# IR_sensor_new_v2.net
KiCad netlist of a schematic drawn in EAGLE
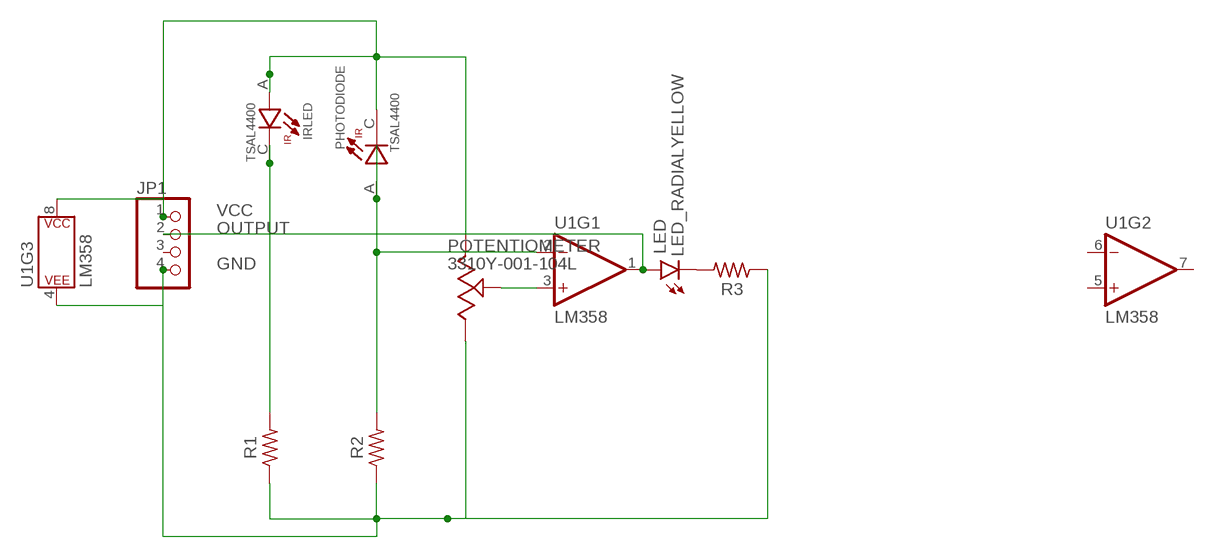
[diagram p0: schematic, sheet 1]

(export (version "E")
  (design (tool "Eeschema 10.0.6"))
  (components
    (comp (ref "IRLED")
      (value "TSAL4400")
      (footprint "eagle-import:LEDRD254W45D335H610")
      (fields (field (name "MF") "Vishay Semiconductor"))
      (libsource (lib "eagle-import") (part "TSAL4400"))
    )
    (comp (ref "JP1")
      (value "PINHD-1X4/90")
      (footprint "eagle-import:1X04_90")
      (libsource (lib "eagle-import") (part "PINHD-1X4/90"))
    )
    (comp (ref "LED")
      (value "LED_RADIALYELLOW")
      (footprint "eagle-import:LEDRD254W60D565H860B_Y")
      (libsource (lib "eagle-import") (part "LED_RADIALYELLOW"))
    )
    (comp (ref "PHOTODIODE")
      (value "TSAL4400")
      (footprint "eagle-import:LEDRD254W45D335H610")
      (fields (field (name "MF") "Vishay Semiconductor"))
      (libsource (lib "eagle-import") (part "TSAL4400"))
    )
    (comp (ref "POTENTIOMETER")
      (value "3310Y-001-104L")
      (footprint "eagle-import:3310Y-001-104L-ND")
      (fields
        (field (name "DIGIKEY_PARTNO") "3310Y-001-104L-ND")
        (field (name "MANUFACTURER") "Bourns Inc.")
        (field (name "CREATED_BY") " PCBLayout.com")
      )
      (libsource (lib "eagle-import") (part "3310Y-001-104L"))
    )
    (comp (ref "R1")
      (value "R-US_AXIAL-7.2MM-PITCH")
      (footprint "eagle-import:RESAD724W46L381D178B")
      (libsource (lib "eagle-import") (part "R-USAXIAL-7.2MM-PITCH_"))
    )
    (comp (ref "R2")
      (value "R-US_AXIAL-7.2MM-PITCH")
      (footprint "eagle-import:RESAD724W46L381D178B")
      (libsource (lib "eagle-import") (part "R-USAXIAL-7.2MM-PITCH_"))
    )
    (comp (ref "R3")
      (value "R-US_AXIAL-7.2MM-PITCH")
      (footprint "eagle-import:RESAD724W46L381D178B")
      (libsource (lib "eagle-import") (part "R-USAXIAL-7.2MM-PITCH_"))
    )
    (comp (ref "U1")
      (value "LM358")
      (footprint "eagle-import:DIP08-KIT")
      (libsource (lib "eagle-import") (part "LM358KIT"))
    )
  )
  (nets
    (net (code "1") (name "/GND") (class "Default")
      (node (ref "JP1") (pin "4") (pinfunction "4_4") (pintype "passive"))
      (node (ref "POTENTIOMETER") (pin "3") (pinfunction "3_3") (pintype "passive"))
      (node (ref "R1") (pin "1") (pinfunction "1_1") (pintype "passive"))
      (node (ref "R2") (pin "1") (pinfunction "1_1") (pintype "passive"))
      (node (ref "R3") (pin "1") (pinfunction "1_1") (pintype "passive"))
      (node (ref "U1") (pin "4") (pinfunction "P$V-_4") (pintype "bidirectional"))
    )
    (net (code "2") (name "/OUTPUT") (class "Default")
      (node (ref "JP1") (pin "2") (pinfunction "2_2") (pintype "passive"))
      (node (ref "LED") (pin "A") (pinfunction "A_A") (pintype "passive"))
      (node (ref "U1") (pin "1") (pinfunction "OUT_1") (pintype "output"))
    )
    (net (code "3") (name "/VCC") (class "Default")
      (node (ref "IRLED") (pin "A") (pinfunction "A_A") (pintype "passive"))
      (node (ref "JP1") (pin "1") (pinfunction "1_1") (pintype "passive"))
      (node (ref "PHOTODIODE") (pin "C") (pinfunction "C_C") (pintype "passive"))
      (node (ref "POTENTIOMETER") (pin "1") (pinfunction "1_1") (pintype "passive"))
      (node (ref "U1") (pin "8") (pinfunction "P$V+_8") (pintype "bidirectional"))
    )
    (net (code "4") (name "Net-(IRLED-PadC)") (class "Default")
      (node (ref "IRLED") (pin "C") (pinfunction "C_C") (pintype "passive"))
      (node (ref "R1") (pin "2") (pinfunction "2_2") (pintype "passive"))
    )
    (net (code "5") (name "Net-(LED-PadC)") (class "Default")
      (node (ref "LED") (pin "C") (pinfunction "C_C") (pintype "passive"))
      (node (ref "R3") (pin "2") (pinfunction "2_2") (pintype "passive"))
    )
    (net (code "6") (name "Net-(U1A-+IN)") (class "Default")
      (node (ref "POTENTIOMETER") (pin "2") (pinfunction "2_2") (pintype "passive"))
      (node (ref "U1") (pin "3") (pinfunction "+IN_3") (pintype "input"))
    )
    (net (code "7") (name "Net-(U1A--IN)") (class "Default")
      (node (ref "PHOTODIODE") (pin "A") (pinfunction "A_A") (pintype "passive"))
      (node (ref "R2") (pin "2") (pinfunction "2_2") (pintype "passive"))
      (node (ref "U1") (pin "2") (pinfunction "-IN_2") (pintype "input"))
    )
    (net (code "8") (name "unconnected-(JP1-Pad3)") (class "Default")
      (node (ref "JP1") (pin "3") (pinfunction "3_3") (pintype "passive"))
    )
    (net (code "9") (name "unconnected-(U1B-+IN-Pad5)") (class "Default")
      (node (ref "U1") (pin "5") (pinfunction "+IN_5") (pintype "input"))
    )
    (net (code "10") (name "unconnected-(U1B--IN-Pad6)") (class "Default")
      (node (ref "U1") (pin "6") (pinfunction "-IN_6") (pintype "input"))
    )
    (net (code "11") (name "unconnected-(U1B-OUT-Pad7)") (class "Default")
      (node (ref "U1") (pin "7") (pinfunction "OUT_7") (pintype "output"))
    )
  )
)
